# ST1Sxx.net
KiCad netlist of a schematic drawn in Altium Designer
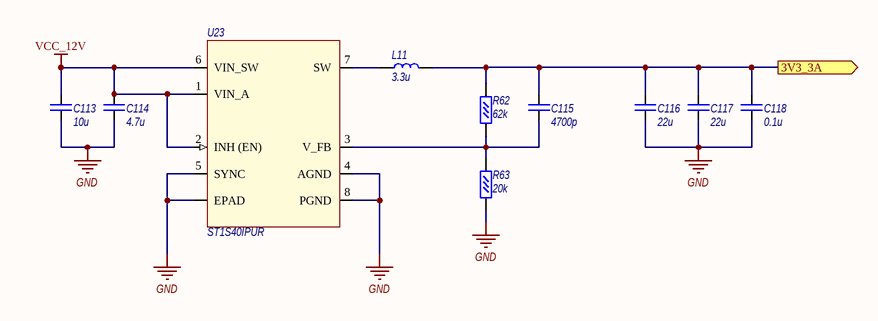
[diagram p0: ST1Sxx.SchDoc]

(export (version "E")
  (design (tool "Eeschema 10.0.6"))
  (components
    (comp (ref "C113")
      (value "10u")
      (footprint "SMD_components:C0805")
      (description "Chip Capacitor 0805")
      (fields (field (name "VOLTAGE") "50В") (field (name "TOLERANCE") "10%"))
      (libsource (lib "Passives") (part "C0805"))
    )
    (comp (ref "C114")
      (value "4.7u")
      (footprint "SMD_components:C0805")
      (description "Chip Capacitor 0805")
      (fields (field (name "VOLTAGE") "50В") (field (name "TOLERANCE") "10%"))
      (libsource (lib "Passives") (part "C0805"))
    )
    (comp (ref "C115")
      (value "4700p")
      (footprint "SMD_components:C0402")
      (description "Chip Capacitor 0402")
      (fields (field (name "VOLTAGE") "6.3В") (field (name "TOLERANCE") "10%"))
      (libsource (lib "Passives") (part "C0402"))
    )
    (comp (ref "C116")
      (value "22u")
      (footprint "SMD_components:C0603")
      (description "Chip Capacitor 0603")
      (fields (field (name "VOLTAGE") "6.3В") (field (name "TOLERANCE") "10%"))
      (libsource (lib "Passives") (part "C0603"))
    )
    (comp (ref "C117")
      (value "22u")
      (footprint "SMD_components:C0603")
      (description "Chip Capacitor 0603")
      (fields (field (name "VOLTAGE") "6.3В") (field (name "TOLERANCE") "10%"))
      (libsource (lib "Passives") (part "C0603"))
    )
    (comp (ref "C118")
      (value "0.1u")
      (footprint "SMD_components:C0603")
      (description "Chip Capacitor 0603")
      (fields (field (name "VOLTAGE") "6.3В") (field (name "TOLERANCE") "10%"))
      (libsource (lib "Passives") (part "C0603"))
    )
    (comp (ref "L11")
      (value "3.3u")
      (footprint "SMD_components:SRP4020TA")
      (description "Shielded Power Inductor")
      (fields (field (name "PARTNUMBER") "SRP4020TA-3R3M") (field (name "MANUFACTURER") "Bourns Inc."))
      (libsource (lib "Passives") (part "SRP4020TA"))
    )
    (comp (ref "R62")
      (value "62k")
      (footprint "SMD_components:R0402")
      (description "Chip Resistor 0402, 0.063 W")
      (fields (field (name "POWER") "0.063Вт") (field (name "TOLERANCE") "1%"))
      (libsource (lib "Passives") (part "R0402_0.063"))
    )
    (comp (ref "R63")
      (value "20k")
      (footprint "SMD_components:R0402")
      (description "Chip Resistor 0402, 0.063 W")
      (fields (field (name "POWER") "0.063Вт") (field (name "TOLERANCE") "1%"))
      (libsource (lib "Passives") (part "R0402_0.063"))
    )
    (comp (ref "U23")
      (value "Микросхема, ST1S40IPUR")
      (footprint "SON80P400X400X100-9N-D")
      (description "3 A, 900 kHz, monolithic synchronous step-down regulator IC")
      (fields (field (name "MANUFACTURER") "STMicroelectronics") (field (name "PARTNUMBER") "ST1S40IPUR"))
      (libsource (lib "IC") (part "ST1S10PHR"))
    )
  )
  (nets
    (net (code "1") (name "/3V3_3A") (class "Default")
      (node (ref "C115") (pin "2") (pinfunction "2_2") (pintype "passive"))
      (node (ref "C116") (pin "2") (pinfunction "2_2") (pintype "passive"))
      (node (ref "C117") (pin "2") (pinfunction "2_2") (pintype "passive"))
      (node (ref "C118") (pin "2") (pinfunction "2_2") (pintype "passive"))
      (node (ref "L11") (pin "2") (pinfunction "2_2") (pintype "passive"))
      (node (ref "R62") (pin "2") (pinfunction "2_2") (pintype "passive"))
    )
    (net (code "2") (name "GND") (class "Default")
      (node (ref "C113") (pin "1") (pinfunction "1_1") (pintype "passive"))
      (node (ref "C114") (pin "1") (pinfunction "1_1") (pintype "passive"))
      (node (ref "C116") (pin "1") (pinfunction "1_1") (pintype "passive"))
      (node (ref "C117") (pin "1") (pinfunction "1_1") (pintype "passive"))
      (node (ref "C118") (pin "1") (pinfunction "1_1") (pintype "passive"))
      (node (ref "R63") (pin "1") (pinfunction "1_1") (pintype "passive"))
      (node (ref "U23") (pin "0") (pinfunction "EPAD_0") (pintype "passive"))
      (node (ref "U23") (pin "4") (pinfunction "AGND_4") (pintype "passive"))
      (node (ref "U23") (pin "5") (pinfunction "SYNC_5") (pintype "passive"))
      (node (ref "U23") (pin "8") (pinfunction "PGND_8") (pintype "passive"))
    )
    (net (code "3") (name "Net-(U23-SW)") (class "Default")
      (node (ref "L11") (pin "1") (pinfunction "1_1") (pintype "passive"))
      (node (ref "U23") (pin "7") (pinfunction "SW_7") (pintype "passive"))
    )
    (net (code "4") (name "Net-(U23-V_FB)") (class "Default")
      (node (ref "C115") (pin "1") (pinfunction "1_1") (pintype "passive"))
      (node (ref "R62") (pin "1") (pinfunction "1_1") (pintype "passive"))
      (node (ref "R63") (pin "2") (pinfunction "2_2") (pintype "passive"))
      (node (ref "U23") (pin "3") (pinfunction "V_FB_3") (pintype "passive"))
    )
    (net (code "5") (name "VCC_12V") (class "Default")
      (node (ref "C113") (pin "2") (pinfunction "2_2") (pintype "passive"))
      (node (ref "C114") (pin "2") (pinfunction "2_2") (pintype "passive"))
      (node (ref "U23") (pin "1") (pinfunction "VIN_A_1") (pintype "passive"))
      (node (ref "U23") (pin "2") (pinfunction "INH_(EN)_2") (pintype "input"))
      (node (ref "U23") (pin "6") (pinfunction "VIN_SW_6") (pintype "passive"))
    )
  )
)
